# Power_Supplies.net
KiCad netlist of a schematic drawn in Altium Designer
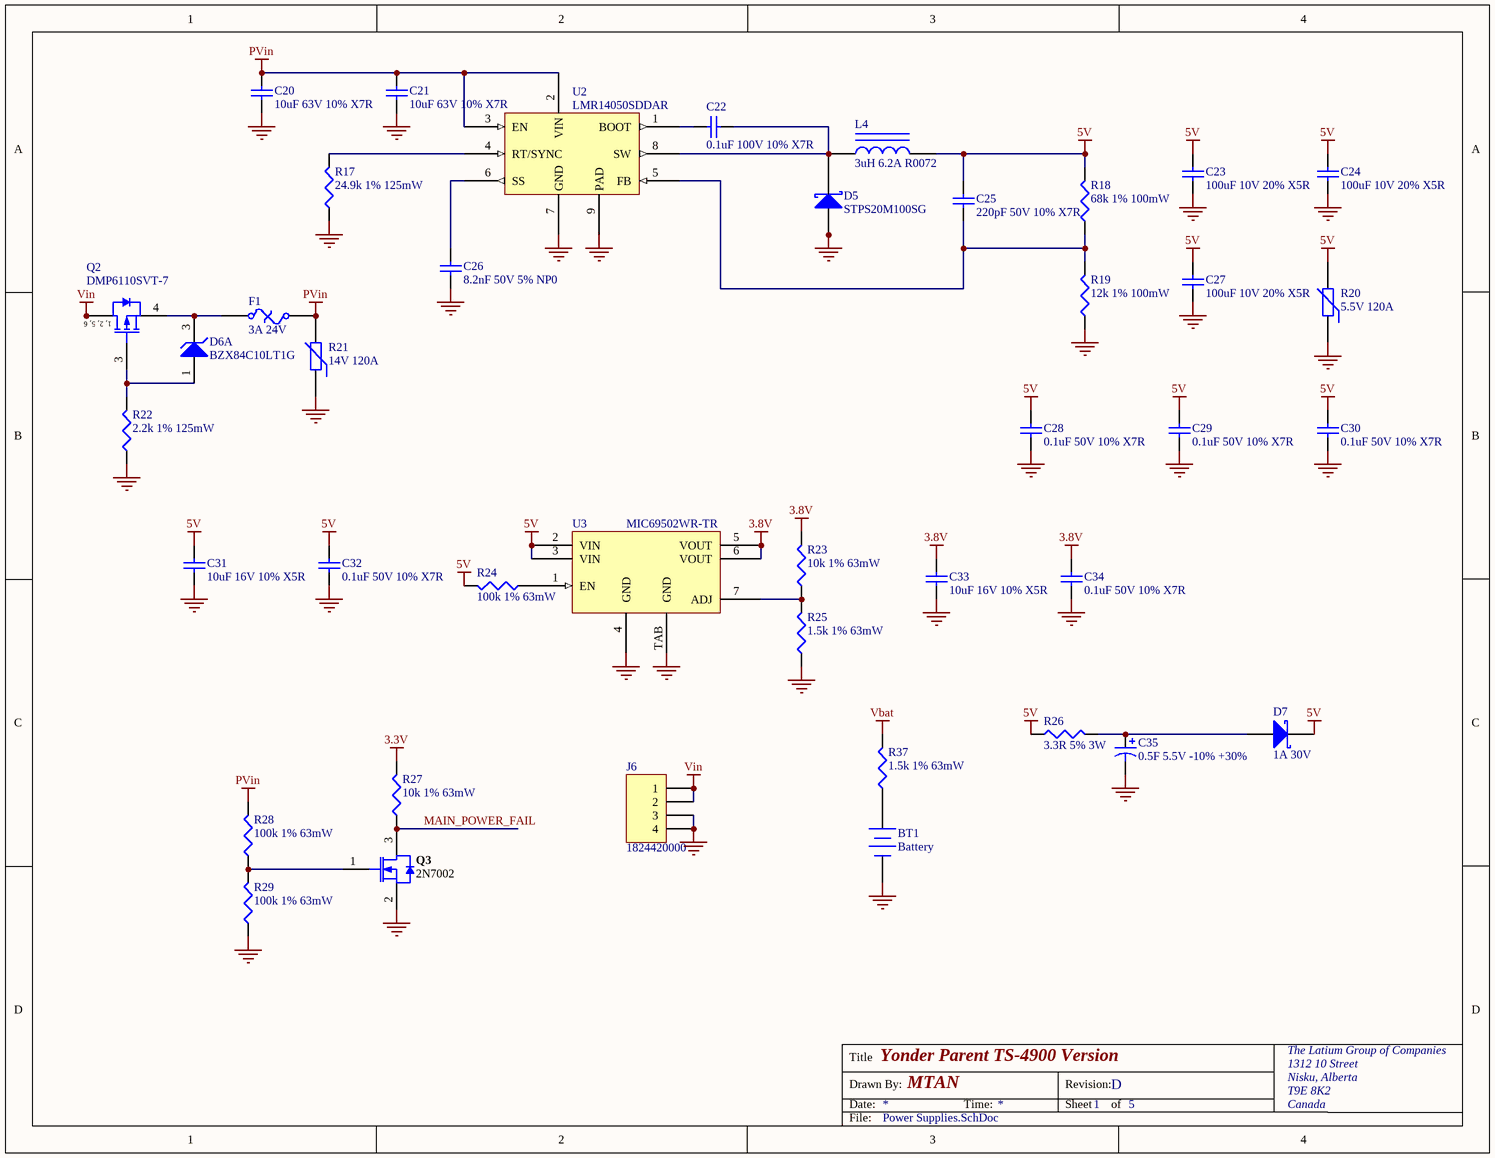
[diagram p0: Power Supplies.SchDoc]

(export (version "E")
  (design (tool "Eeschema 10.0.6"))
  (components
    (comp (ref "BT1")
      (value "Battery")
      (footprint "MPD BS-7")
      (description "BATTERY HOLDER COIN 20MM PC PIN")
      (fields
        (field (name "MANUFACTURER") "MPD (Memory Protection Devices)")
        (field (name "MANUFACTURER PART NUMBER") "BS-7")
      )
      (libsource (lib "Miscellaneous Devices") (part "Battery"))
    )
    (comp (ref "C20")
      (value "10uF 63V 10% X7R")
      (footprint "C1210_L")
      (description "Capacitor")
      (libsource (lib "Miscellaneous Devices") (part "Cap"))
    )
    (comp (ref "C21")
      (value "10uF 63V 10% X7R")
      (footprint "C1210_L")
      (description "Capacitor")
      (libsource (lib "Miscellaneous Devices") (part "Cap"))
    )
    (comp (ref "C22")
      (value "0.1uF 100V 10% X7R")
      (footprint "C0805")
      (description "Capacitor")
      (libsource (lib "Miscellaneous Devices") (part "Cap"))
    )
    (comp (ref "C23")
      (value "100uF 10V 20% X5R")
      (footprint "C1210_L")
      (description "Capacitor")
      (libsource (lib "Miscellaneous Devices") (part "Cap"))
    )
    (comp (ref "C24")
      (value "100uF 10V 20% X5R")
      (footprint "C1210_L")
      (description "Capacitor")
      (libsource (lib "Miscellaneous Devices") (part "Cap"))
    )
    (comp (ref "C25")
      (value "220pF 50V 10% X7R")
      (footprint "1608[0603]")
      (description "Capacitor")
      (libsource (lib "Miscellaneous Devices") (part "Cap"))
    )
    (comp (ref "C26")
      (value "8.2nF 50V 5% NP0")
      (footprint "1608[0603]")
      (description "Capacitor")
      (libsource (lib "Miscellaneous Devices") (part "Cap"))
    )
    (comp (ref "C27")
      (value "100uF 10V 20% X5R")
      (footprint "C1210_L")
      (description "Capacitor")
      (libsource (lib "Miscellaneous Devices") (part "Cap"))
    )
    (comp (ref "C28")
      (value "0.1uF 50V 10% X7R")
      (footprint "CAPC1005L")
      (description "Capacitor")
      (libsource (lib "Miscellaneous Devices") (part "Cap"))
    )
    (comp (ref "C29")
      (value "0.1uF 50V 10% X7R")
      (footprint "CAPC1005L")
      (description "Capacitor")
      (libsource (lib "Miscellaneous Devices") (part "Cap"))
    )
    (comp (ref "C30")
      (value "0.1uF 50V 10% X7R")
      (footprint "CAPC1005L")
      (description "Capacitor")
      (libsource (lib "Miscellaneous Devices") (part "Cap"))
    )
    (comp (ref "C31")
      (value "10uF 16V 10% X5R")
      (footprint "C0805")
      (description "Capacitor")
      (libsource (lib "Miscellaneous Devices") (part "Cap"))
    )
    (comp (ref "C32")
      (value "0.1uF 50V 10% X7R")
      (footprint "CAPC1005L")
      (description "Capacitor")
      (libsource (lib "Miscellaneous Devices") (part "Cap"))
    )
    (comp (ref "C33")
      (value "10uF 16V 10% X5R")
      (footprint "C0805")
      (description "Capacitor")
      (libsource (lib "Miscellaneous Devices") (part "Cap"))
    )
    (comp (ref "C34")
      (value "0.1uF 50V 10% X7R")
      (footprint "CAPC1005L")
      (description "Capacitor")
      (libsource (lib "Miscellaneous Devices") (part "Cap"))
    )
    (comp (ref "C35")
      (value "0.5F 5.5V -10% +30%")
      (footprint "Illinois SuperCap")
      (description "CAP 500MF -10% +30% 5.5V TH")
      (fields
        (field (name "MANUFACTURER") "Illinois Capacitor")
        (field (name "MANUFACTURER PART NUMBER") "DGH504Q5R5")
      )
      (libsource (lib "Miscellaneous Devices") (part "Cap Pol1"))
    )
    (comp (ref "D5")
      (value "STPS20M100SG")
      (footprint "ONSC-D2PAK-3-418AJ_A_V")
      (description "DIODE SCHOTTKY 100V 20A D2PAK")
      (fields (field (name "MANUFACTURER") "STMicroelectronics"))
      (libsource (lib "Infineon Discrete Diode") (part "BAS70"))
    )
    (comp (ref "D6")
      (value "BZX84C10LT1G")
      (footprint "SOT23-3_L")
      (description "DIODE ZENER 10V 225MW SOT23-3")
      (fields (field (name "MANUFACTURER") "On Semiconductor"))
      (libsource (lib "ON Semi Zener Diodes") (part "BZX84C10LT1G"))
    )
    (comp (ref "D7")
      (value "1A 30V")
      (footprint "SOD323")
      (description "Schottky Diode")
      (fields
        (field (name "MANUFACTURER") "Toshiba Semiconductor and Storage")
        (field (name "MANUFACTURER PART NUMBER") "CUS10S30,H3F")
      )
      (libsource (lib "Miscellaneous Devices") (part "D Schottky"))
    )
    (comp (ref "F1")
      (value "3A 24V")
      (footprint "2920")
      (description "Thermal Fuse")
      (fields
        (field (name "MANUFACTURER PART NUMBER") "SMDC300F/24-2")
        (field (name "MANUFACTURER") "Littelfuse Inc")
      )
      (libsource (lib "Miscellaneous Devices") (part "Fuse Thermal"))
    )
    (comp (ref "J6")
      (value "1824420000")
      (footprint "1824420000")
      (description "TERM BLK 2POS SIDE ENT 3.5MM PCB")
      (fields (field (name "MANUFACTURER") "Weidmuller"))
      (libsource (lib "Miscellaneous Connectors") (part "Header 4H"))
    )
    (comp (ref "L4")
      (value "3uH 6.2A R0072")
      (footprint "SRU1048")
      (description "FIXED IND 3UH 6.2A 7.2 MOHM SMD")
      (fields
        (field (name "MANUFACTURER PART NUMBER") "SRU1048-3R0Y")
        (field (name "MANUFACTURER") "Bourns Inc")
      )
      (libsource (lib "Miscellaneous Devices") (part "Inductor Iron"))
    )
    (comp (ref "Q2")
      (value "DMP6110SVT-7")
      (footprint "SOT23-6_L")
      (description "MOSFET P-CH 60V TSOT26")
      (fields (field (name "MANUFACTURER") "Diodes Incorporated"))
      (libsource (lib "ON Semi MOSFETs") (part "NTGS3136PT1G"))
    )
    (comp (ref "Q3")
      (value "2N7002")
      (footprint "INF-PG-SOT23_L")
      (description "MOSFET N-CH 60V 115MA SOT-23")
      (fields (field (name "MANUFACTURER") "ON Semiconductor"))
      (libsource (lib "Infineon Power MOSFET") (part "2N7002"))
    )
    (comp (ref "R17")
      (value "24.9k 1% 125mW")
      (footprint "6-0805_L")
      (description "Resistor")
      (libsource (lib "Miscellaneous Devices") (part "Res3"))
    )
    (comp (ref "R18")
      (value "68k 1% 100mW")
      (footprint "J1-0603")
      (description "Resistor")
      (libsource (lib "Miscellaneous Devices") (part "Res3"))
    )
    (comp (ref "R19")
      (value "12k 1% 100mW")
      (footprint "J1-0603")
      (description "Resistor")
      (libsource (lib "Miscellaneous Devices") (part "Res3"))
    )
    (comp (ref "R20")
      (value "5.5V 120A")
      (footprint "6-0805_L")
      (description "VARISTOR 8.2V 120A 0805")
      (fields
        (field (name "MANUFACTURER") "Littelfuse Inc")
        (field (name "MANUFACTURER PART NUMBER") "V5.5MLA0805H")
      )
      (libsource (lib "Miscellaneous Devices") (part "Res Varistor"))
    )
    (comp (ref "R21")
      (value "14V 120A")
      (footprint "6-0805_L")
      (description "VARISTOR 18.1V 120A 0805")
      (fields
        (field (name "MANUFACTURER") "Littelfuse Inc")
        (field (name "MANUFACTURER PART NUMBER") "V14MLA0805NH")
      )
      (libsource (lib "Miscellaneous Devices") (part "Res Varistor"))
    )
    (comp (ref "R22")
      (value "2.2k 1% 125mW")
      (footprint "6-0805_L")
      (description "Resistor")
      (libsource (lib "Miscellaneous Devices") (part "Res3"))
    )
    (comp (ref "R23")
      (value "10k 1% 63mW")
      (footprint "RESC1005L")
      (description "Resistor")
      (libsource (lib "Miscellaneous Devices") (part "Res3"))
    )
    (comp (ref "R24")
      (value "100k 1% 63mW")
      (footprint "RESC1005L")
      (description "Resistor")
      (libsource (lib "Miscellaneous Devices") (part "Res3"))
    )
    (comp (ref "R25")
      (value "1.5k 1% 63mW")
      (footprint "RESC1005L")
      (description "Resistor")
      (libsource (lib "Miscellaneous Devices") (part "Res3"))
    )
    (comp (ref "R26")
      (value "3.3R 5% 3W")
      (footprint "RESC6432AL")
      (description "RES SMD 3.3 OHM 5% 3W 2512")
      (fields
        (field (name "MANUFACTURER") "TE Connectivity Passive Product")
        (field (name "MANUFACTURER PART NUMBER") "35223R3JT")
      )
      (libsource (lib "Miscellaneous Devices") (part "Res3"))
    )
    (comp (ref "R27")
      (value "10k 1% 63mW")
      (footprint "RESC1005L")
      (description "Resistor")
      (libsource (lib "Miscellaneous Devices") (part "Res3"))
    )
    (comp (ref "R28")
      (value "100k 1% 63mW")
      (footprint "RESC1005L")
      (description "Resistor")
      (libsource (lib "Miscellaneous Devices") (part "Res3"))
    )
    (comp (ref "R29")
      (value "100k 1% 63mW")
      (footprint "RESC1005L")
      (description "Resistor")
      (libsource (lib "Miscellaneous Devices") (part "Res3"))
    )
    (comp (ref "R37")
      (value "1.5k 1% 63mW")
      (footprint "RESC1005L")
      (description "Resistor")
      (libsource (lib "Miscellaneous Devices") (part "Res3"))
    )
    (comp (ref "U2")
      (value "LMR14050SDDAR")
      (footprint "MRA08A_L")
      (description "IC REG BUCK ADJUSTABLE 5A 8SOPWR")
      (fields (field (name "MANUFACTURER") "Texas Instruments"))
      (libsource (lib "Latium Component Library") (part "LMR14050"))
    )
    (comp (ref "U3")
      (value "MIC69502WR-TR")
      (footprint "SPak-7")
      (description "IC REG LINEAR POS ADJ 5A SPAK-7")
      (fields (field (name "MANUFACTURER") "Microchip Technology"))
      (libsource (lib "Latium Component Library") (part "MIC69502"))
    )
  )
  (nets
    (net (code "1") (name "/MAIN_POWER_FAIL") (class "Default")
      (node (ref "Q3") (pin "3") (pinfunction "DRAIN_3") (pintype "passive"))
      (node (ref "R27") (pin "1") (pinfunction "1_1") (pintype "passive"))
    )
    (net (code "2") (name "3.3V") (class "Default")
      (node (ref "R27") (pin "2") (pinfunction "2_2") (pintype "passive"))
    )
    (net (code "3") (name "3.8V") (class "Default")
      (node (ref "C33") (pin "1") (pinfunction "1_1") (pintype "passive"))
      (node (ref "C34") (pin "1") (pinfunction "1_1") (pintype "passive"))
      (node (ref "R23") (pin "2") (pinfunction "2_2") (pintype "passive"))
      (node (ref "U3") (pin "5") (pinfunction "VOUT_5") (pintype "power_in"))
      (node (ref "U3") (pin "6") (pinfunction "VOUT_6") (pintype "power_in"))
    )
    (net (code "4") (name "5V") (class "Default")
      (node (ref "C23") (pin "2") (pinfunction "2_2") (pintype "passive"))
      (node (ref "C24") (pin "2") (pinfunction "2_2") (pintype "passive"))
      (node (ref "C25") (pin "2") (pinfunction "2_2") (pintype "passive"))
      (node (ref "C27") (pin "2") (pinfunction "2_2") (pintype "passive"))
      (node (ref "C28") (pin "1") (pinfunction "1_1") (pintype "passive"))
      (node (ref "C29") (pin "1") (pinfunction "1_1") (pintype "passive"))
      (node (ref "C30") (pin "1") (pinfunction "1_1") (pintype "passive"))
      (node (ref "C31") (pin "1") (pinfunction "1_1") (pintype "passive"))
      (node (ref "C32") (pin "1") (pinfunction "1_1") (pintype "passive"))
      (node (ref "D7") (pin "1") (pinfunction "K_1") (pintype "passive"))
      (node (ref "L4") (pin "2") (pinfunction "2_2") (pintype "passive"))
      (node (ref "R18") (pin "2") (pinfunction "2_2") (pintype "passive"))
      (node (ref "R20") (pin "2") (pinfunction "2_2") (pintype "passive"))
      (node (ref "R24") (pin "2") (pinfunction "2_2") (pintype "passive"))
      (node (ref "R26") (pin "1") (pinfunction "1_1") (pintype "passive"))
      (node (ref "U3") (pin "2") (pinfunction "VIN_2") (pintype "power_in"))
      (node (ref "U3") (pin "3") (pinfunction "VIN_3") (pintype "power_in"))
    )
    (net (code "5") (name "GND") (class "Default")
      (node (ref "BT1") (pin "2") (pinfunction "-_2") (pintype "passive"))
      (node (ref "C20") (pin "1") (pinfunction "1_1") (pintype "passive"))
      (node (ref "C21") (pin "1") (pinfunction "1_1") (pintype "passive"))
      (node (ref "C23") (pin "1") (pinfunction "1_1") (pintype "passive"))
      (node (ref "C24") (pin "1") (pinfunction "1_1") (pintype "passive"))
      (node (ref "C26") (pin "1") (pinfunction "1_1") (pintype "passive"))
      (node (ref "C27") (pin "1") (pinfunction "1_1") (pintype "passive"))
      (node (ref "C28") (pin "2") (pinfunction "2_2") (pintype "passive"))
      (node (ref "C29") (pin "2") (pinfunction "2_2") (pintype "passive"))
      (node (ref "C30") (pin "2") (pinfunction "2_2") (pintype "passive"))
      (node (ref "C31") (pin "2") (pinfunction "2_2") (pintype "passive"))
      (node (ref "C32") (pin "2") (pinfunction "2_2") (pintype "passive"))
      (node (ref "C33") (pin "2") (pinfunction "2_2") (pintype "passive"))
      (node (ref "C34") (pin "2") (pinfunction "2_2") (pintype "passive"))
      (node (ref "C35") (pin "2") (pinfunction "2_2") (pintype "passive"))
      (node (ref "D5") (pin "1") (pinfunction "A_1") (pintype "passive"))
      (node (ref "D5") (pin "3") (pinfunction "A_3") (pintype "passive"))
      (node (ref "J6") (pin "3") (pinfunction "3_3") (pintype "passive"))
      (node (ref "J6") (pin "4") (pinfunction "4_4") (pintype "passive"))
      (node (ref "Q3") (pin "2") (pinfunction "SOURCE_2") (pintype "passive"))
      (node (ref "R17") (pin "1") (pinfunction "1_1") (pintype "passive"))
      (node (ref "R19") (pin "1") (pinfunction "1_1") (pintype "passive"))
      (node (ref "R20") (pin "1") (pinfunction "1_1") (pintype "passive"))
      (node (ref "R21") (pin "1") (pinfunction "1_1") (pintype "passive"))
      (node (ref "R22") (pin "1") (pinfunction "1_1") (pintype "passive"))
      (node (ref "R25") (pin "1") (pinfunction "1_1") (pintype "passive"))
      (node (ref "R29") (pin "1") (pinfunction "1_1") (pintype "passive"))
      (node (ref "U2") (pin "7") (pinfunction "GND_7") (pintype "power_in"))
      (node (ref "U2") (pin "9") (pinfunction "PAD_9") (pintype "power_in"))
      (node (ref "U3") (pin "4") (pinfunction "GND_4") (pintype "power_in"))
      (node (ref "U3") (pin "TAB") (pinfunction "GND_TAB") (pintype "power_in"))
    )
    (net (code "6") (name "Net-(BT1-+)") (class "Default")
      (node (ref "BT1") (pin "1") (pinfunction "+_1") (pintype "passive"))
      (node (ref "R37") (pin "1") (pinfunction "1_1") (pintype "passive"))
    )
    (net (code "7") (name "Net-(D5-K)") (class "Default")
      (node (ref "C22") (pin "1") (pinfunction "1_1") (pintype "passive"))
      (node (ref "D5") (pin "4") (pinfunction "K_4") (pintype "passive"))
      (node (ref "L4") (pin "1") (pinfunction "1_1") (pintype "passive"))
      (node (ref "U2") (pin "8") (pinfunction "SW_8") (pintype "output"))
    )
    (net (code "8") (name "Net-(D6A-A)") (class "Default")
      (node (ref "D6") (pin "1") (pinfunction "A_1") (pintype "passive"))
      (node (ref "Q2") (pin "3") (pinfunction "G_3") (pintype "passive"))
      (node (ref "R22") (pin "2") (pinfunction "2_2") (pintype "passive"))
    )
    (net (code "9") (name "Net-(D6A-K)") (class "Default")
      (node (ref "D6") (pin "3") (pinfunction "K_3") (pintype "passive"))
      (node (ref "F1") (pin "1") (pinfunction "1_1") (pintype "passive"))
      (node (ref "Q2") (pin "4") (pinfunction "S_4") (pintype "passive"))
    )
    (net (code "10") (name "Net-(D7-A)") (class "Default")
      (node (ref "C35") (pin "1") (pinfunction "1_1") (pintype "passive"))
      (node (ref "D7") (pin "2") (pinfunction "A_2") (pintype "passive"))
      (node (ref "R26") (pin "2") (pinfunction "2_2") (pintype "passive"))
    )
    (net (code "11") (name "Net-(Q3-GATE)") (class "Default")
      (node (ref "Q3") (pin "1") (pinfunction "GATE_1") (pintype "passive"))
      (node (ref "R28") (pin "1") (pinfunction "1_1") (pintype "passive"))
      (node (ref "R29") (pin "2") (pinfunction "2_2") (pintype "passive"))
    )
    (net (code "12") (name "Net-(U2-BOOT)") (class "Default")
      (node (ref "C22") (pin "2") (pinfunction "2_2") (pintype "passive"))
      (node (ref "U2") (pin "1") (pinfunction "BOOT_1") (pintype "output"))
    )
    (net (code "13") (name "Net-(U2-FB)") (class "Default")
      (node (ref "C25") (pin "1") (pinfunction "1_1") (pintype "passive"))
      (node (ref "R18") (pin "1") (pinfunction "1_1") (pintype "passive"))
      (node (ref "R19") (pin "2") (pinfunction "2_2") (pintype "passive"))
      (node (ref "U2") (pin "5") (pinfunction "FB_5") (pintype "input"))
    )
    (net (code "14") (name "Net-(U2-RT{slash}SYNC)") (class "Default")
      (node (ref "R17") (pin "2") (pinfunction "2_2") (pintype "passive"))
      (node (ref "U2") (pin "4") (pinfunction "RT/SYNC_4") (pintype "input"))
    )
    (net (code "15") (name "Net-(U2-SS)") (class "Default")
      (node (ref "C26") (pin "2") (pinfunction "2_2") (pintype "passive"))
      (node (ref "U2") (pin "6") (pinfunction "SS_6") (pintype "output"))
    )
    (net (code "16") (name "Net-(U3-ADJ)") (class "Default")
      (node (ref "R23") (pin "1") (pinfunction "1_1") (pintype "passive"))
      (node (ref "R25") (pin "2") (pinfunction "2_2") (pintype "passive"))
      (node (ref "U3") (pin "7") (pinfunction "ADJ_7") (pintype "passive"))
    )
    (net (code "17") (name "Net-(U3-EN)") (class "Default")
      (node (ref "R24") (pin "1") (pinfunction "1_1") (pintype "passive"))
      (node (ref "U3") (pin "1") (pinfunction "EN_1") (pintype "input"))
    )
    (net (code "18") (name "PVin") (class "Default")
      (node (ref "C20") (pin "2") (pinfunction "2_2") (pintype "passive"))
      (node (ref "C21") (pin "2") (pinfunction "2_2") (pintype "passive"))
      (node (ref "F1") (pin "2") (pinfunction "2_2") (pintype "passive"))
      (node (ref "R21") (pin "2") (pinfunction "2_2") (pintype "passive"))
      (node (ref "R28") (pin "2") (pinfunction "2_2") (pintype "passive"))
      (node (ref "U2") (pin "2") (pinfunction "VIN_2") (pintype "power_in"))
      (node (ref "U2") (pin "3") (pinfunction "EN_3") (pintype "input"))
    )
    (net (code "19") (name "Vbat") (class "Default")
      (node (ref "R37") (pin "2") (pinfunction "2_2") (pintype "passive"))
    )
    (net (code "20") (name "Vin") (class "Default")
      (node (ref "J6") (pin "1") (pinfunction "1_1") (pintype "passive"))
      (node (ref "J6") (pin "2") (pinfunction "2_2") (pintype "passive"))
      (node (ref "Q2") (pin "1") (pinfunction "D_1") (pintype "passive"))
      (node (ref "Q2") (pin "2") (pinfunction "D_2") (pintype "passive"))
      (node (ref "Q2") (pin "5") (pinfunction "D_5") (pintype "passive"))
      (node (ref "Q2") (pin "6") (pinfunction "D_6") (pintype "passive"))
    )
  )
)
